# rf_front.net
KiCad netlist of a schematic drawn in EAGLE
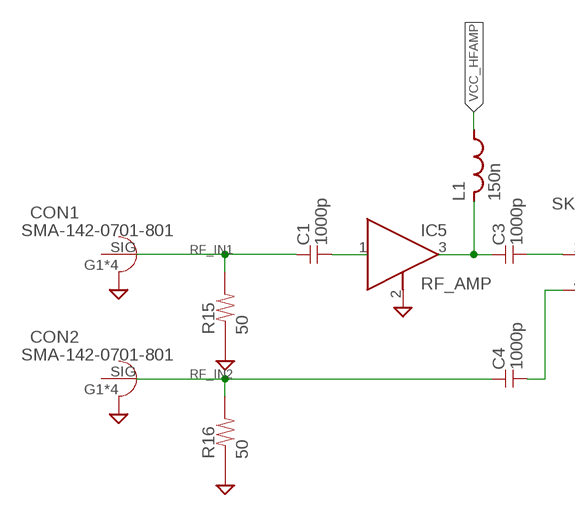
[diagram p0: schematic, sheet 1, part 1 of 2]
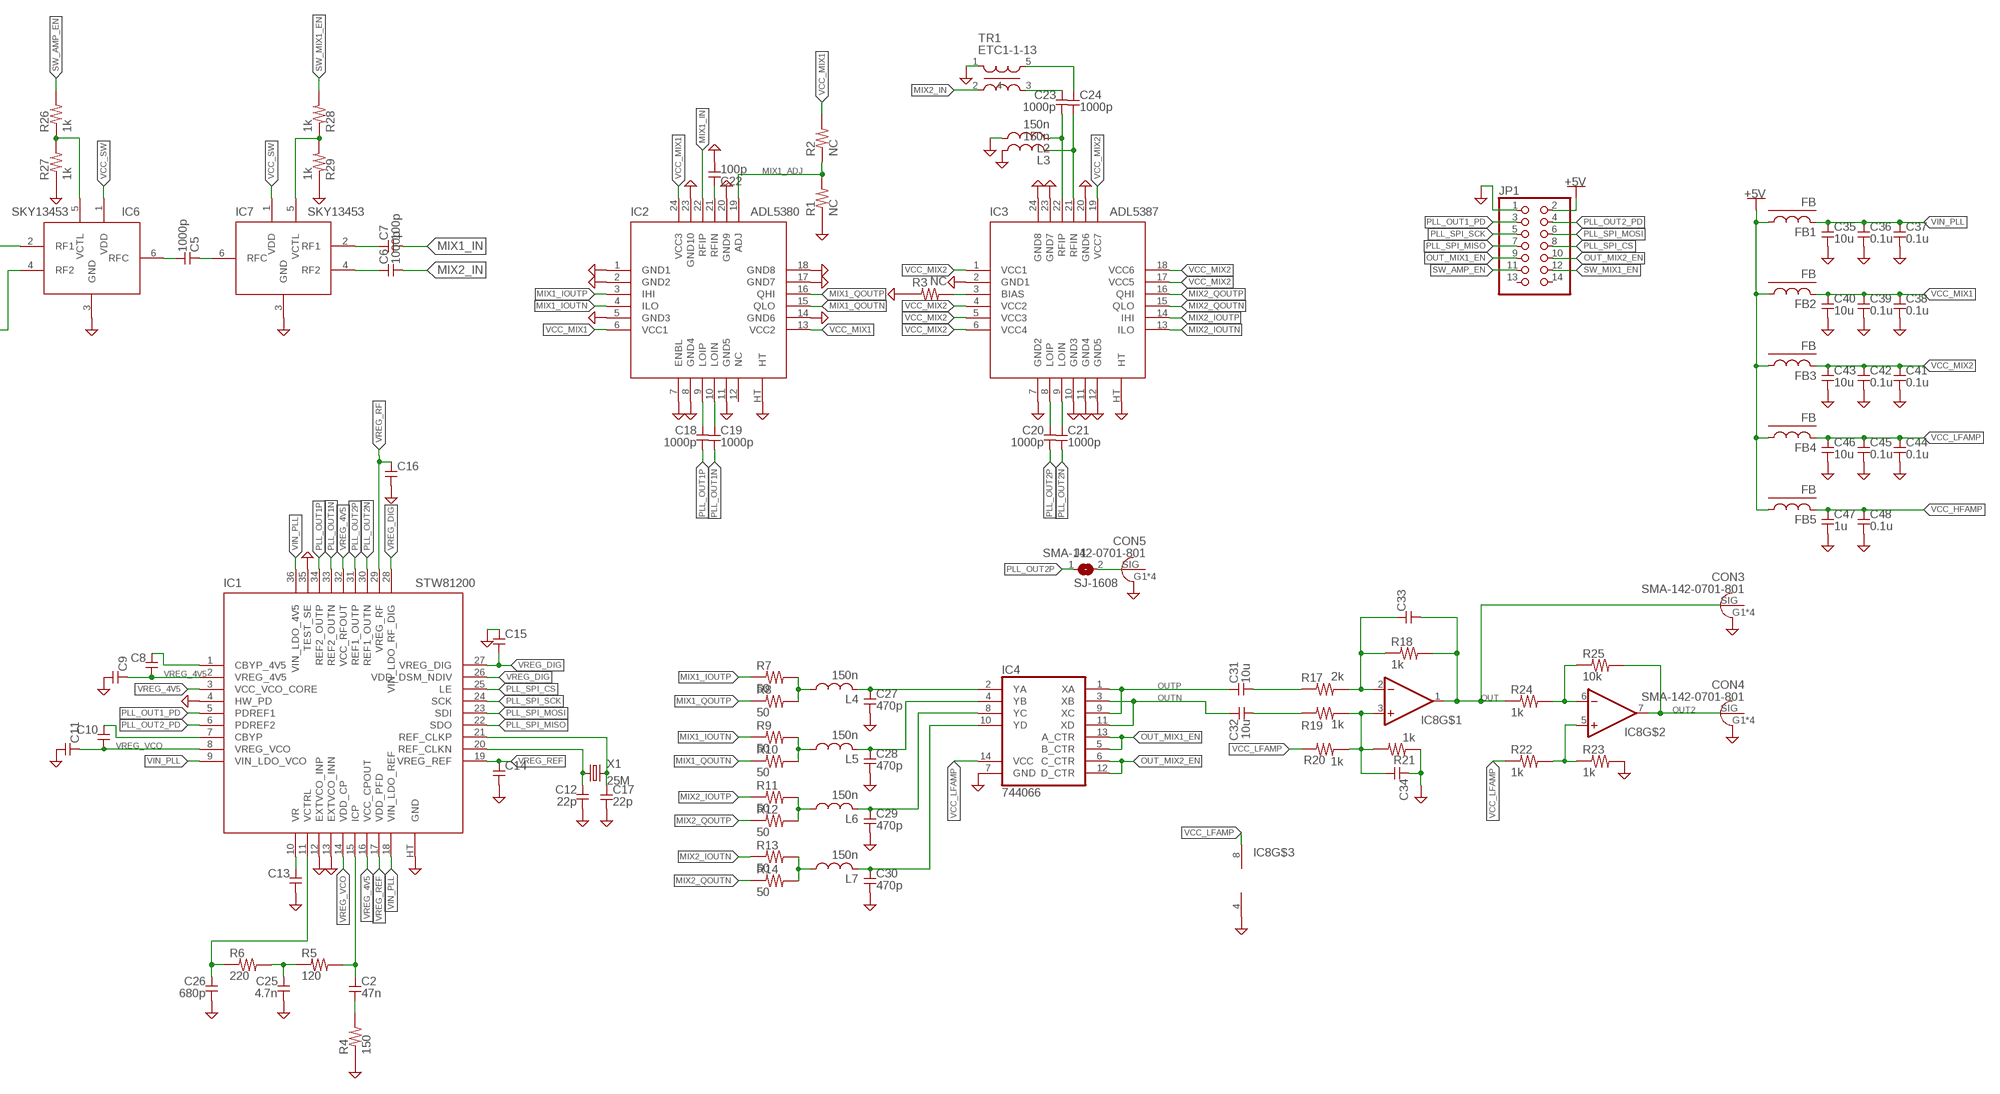
[diagram p1: schematic, sheet 1, part 2 of 2]

(export (version "E")
  (design (tool "Eeschema 10.0.6"))
  (components
    (comp (ref "C1")
      (value "1000p")
      (footprint "eagle-import:1608")
      (libsource (lib "eagle-import") (part "C-1608"))
    )
    (comp (ref "C2")
      (value "47n")
      (footprint "eagle-import:1608")
      (libsource (lib "eagle-import") (part "C-1608"))
    )
    (comp (ref "C3")
      (value "1000p")
      (footprint "eagle-import:1608")
      (libsource (lib "eagle-import") (part "C-1608"))
    )
    (comp (ref "C4")
      (value "1000p")
      (footprint "eagle-import:1608")
      (libsource (lib "eagle-import") (part "C-1608"))
    )
    (comp (ref "C5")
      (value "1000p")
      (footprint "eagle-import:1608")
      (libsource (lib "eagle-import") (part "C-1608"))
    )
    (comp (ref "C6")
      (value "1000p")
      (footprint "eagle-import:1608")
      (libsource (lib "eagle-import") (part "C-1608"))
    )
    (comp (ref "C7")
      (value "100p")
      (footprint "eagle-import:1608")
      (libsource (lib "eagle-import") (part "C-1608"))
    )
    (comp (ref "C8")
      (value "C-1608")
      (footprint "eagle-import:1608")
      (libsource (lib "eagle-import") (part "C-1608"))
    )
    (comp (ref "C9")
      (value "C-1608")
      (footprint "eagle-import:1608")
      (libsource (lib "eagle-import") (part "C-1608"))
    )
    (comp (ref "C10")
      (value "C-1608")
      (footprint "eagle-import:1608")
      (libsource (lib "eagle-import") (part "C-1608"))
    )
    (comp (ref "C11")
      (value "C-1608")
      (footprint "eagle-import:1608")
      (libsource (lib "eagle-import") (part "C-1608"))
    )
    (comp (ref "C12")
      (value "22p")
      (footprint "eagle-import:1608")
      (libsource (lib "eagle-import") (part "C-1608"))
    )
    (comp (ref "C13")
      (value "C-1608")
      (footprint "eagle-import:1608")
      (libsource (lib "eagle-import") (part "C-1608"))
    )
    (comp (ref "C14")
      (value "C-1608")
      (footprint "eagle-import:1608")
      (libsource (lib "eagle-import") (part "C-1608"))
    )
    (comp (ref "C15")
      (value "C-1608")
      (footprint "eagle-import:1608")
      (libsource (lib "eagle-import") (part "C-1608"))
    )
    (comp (ref "C16")
      (value "C-1608")
      (footprint "eagle-import:1608")
      (libsource (lib "eagle-import") (part "C-1608"))
    )
    (comp (ref "C17")
      (value "22p")
      (footprint "eagle-import:1608")
      (libsource (lib "eagle-import") (part "C-1608"))
    )
    (comp (ref "C18")
      (value "1000p")
      (footprint "eagle-import:1608")
      (libsource (lib "eagle-import") (part "C-1608"))
    )
    (comp (ref "C19")
      (value "1000p")
      (footprint "eagle-import:1608")
      (libsource (lib "eagle-import") (part "C-1608"))
    )
    (comp (ref "C20")
      (value "1000p")
      (footprint "eagle-import:1608")
      (libsource (lib "eagle-import") (part "C-1608"))
    )
    (comp (ref "C21")
      (value "1000p")
      (footprint "eagle-import:1608")
      (libsource (lib "eagle-import") (part "C-1608"))
    )
    (comp (ref "C22")
      (value "100p")
      (footprint "eagle-import:1608")
      (libsource (lib "eagle-import") (part "C-1608"))
    )
    (comp (ref "C23")
      (value "1000p")
      (footprint "eagle-import:1608")
      (libsource (lib "eagle-import") (part "C-1608"))
    )
    (comp (ref "C24")
      (value "1000p")
      (footprint "eagle-import:1608")
      (libsource (lib "eagle-import") (part "C-1608"))
    )
    (comp (ref "C25")
      (value "4.7n")
      (footprint "eagle-import:1608")
      (libsource (lib "eagle-import") (part "C-1608"))
    )
    (comp (ref "C26")
      (value "680p")
      (footprint "eagle-import:1608")
      (libsource (lib "eagle-import") (part "C-1608"))
    )
    (comp (ref "C27")
      (value "470p")
      (footprint "eagle-import:1608")
      (libsource (lib "eagle-import") (part "C-1608"))
    )
    (comp (ref "C28")
      (value "470p")
      (footprint "eagle-import:1608")
      (libsource (lib "eagle-import") (part "C-1608"))
    )
    (comp (ref "C29")
      (value "470p")
      (footprint "eagle-import:1608")
      (libsource (lib "eagle-import") (part "C-1608"))
    )
    (comp (ref "C30")
      (value "470p")
      (footprint "eagle-import:1608")
      (libsource (lib "eagle-import") (part "C-1608"))
    )
    (comp (ref "C31")
      (value "10u")
      (footprint "eagle-import:2012")
      (libsource (lib "eagle-import") (part "C-2012"))
    )
    (comp (ref "C32")
      (value "10u")
      (footprint "eagle-import:2012")
      (libsource (lib "eagle-import") (part "C-2012"))
    )
    (comp (ref "C33")
      (value "C-1608")
      (footprint "eagle-import:1608")
      (libsource (lib "eagle-import") (part "C-1608"))
    )
    (comp (ref "C34")
      (value "C-1608")
      (footprint "eagle-import:1608")
      (libsource (lib "eagle-import") (part "C-1608"))
    )
    (comp (ref "C35")
      (value "10u")
      (footprint "eagle-import:2012")
      (libsource (lib "eagle-import") (part "C-2012"))
    )
    (comp (ref "C36")
      (value "0.1u")
      (footprint "eagle-import:1608")
      (libsource (lib "eagle-import") (part "C-1608"))
    )
    (comp (ref "C37")
      (value "0.1u")
      (footprint "eagle-import:1608")
      (libsource (lib "eagle-import") (part "C-1608"))
    )
    (comp (ref "C38")
      (value "0.1u")
      (footprint "eagle-import:1608")
      (libsource (lib "eagle-import") (part "C-1608"))
    )
    (comp (ref "C39")
      (value "0.1u")
      (footprint "eagle-import:1608")
      (libsource (lib "eagle-import") (part "C-1608"))
    )
    (comp (ref "C40")
      (value "10u")
      (footprint "eagle-import:2012")
      (libsource (lib "eagle-import") (part "C-2012"))
    )
    (comp (ref "C41")
      (value "0.1u")
      (footprint "eagle-import:1608")
      (libsource (lib "eagle-import") (part "C-1608"))
    )
    (comp (ref "C42")
      (value "0.1u")
      (footprint "eagle-import:1608")
      (libsource (lib "eagle-import") (part "C-1608"))
    )
    (comp (ref "C43")
      (value "10u")
      (footprint "eagle-import:2012")
      (libsource (lib "eagle-import") (part "C-2012"))
    )
    (comp (ref "C44")
      (value "0.1u")
      (footprint "eagle-import:1608")
      (libsource (lib "eagle-import") (part "C-1608"))
    )
    (comp (ref "C45")
      (value "0.1u")
      (footprint "eagle-import:1608")
      (libsource (lib "eagle-import") (part "C-1608"))
    )
    (comp (ref "C46")
      (value "10u")
      (footprint "eagle-import:2012")
      (libsource (lib "eagle-import") (part "C-2012"))
    )
    (comp (ref "C47")
      (value "1u")
      (footprint "eagle-import:1608")
      (libsource (lib "eagle-import") (part "C-1608"))
    )
    (comp (ref "C48")
      (value "0.1u")
      (footprint "eagle-import:1608")
      (libsource (lib "eagle-import") (part "C-1608"))
    )
    (comp (ref "CON1")
      (value "SMA-142-0701-801")
      (footprint "eagle-import:SMA-142-0701-801")
      (libsource (lib "eagle-import") (part "SMA-142-0701-801"))
    )
    (comp (ref "CON2")
      (value "SMA-142-0701-801")
      (footprint "eagle-import:SMA-142-0701-801")
      (libsource (lib "eagle-import") (part "SMA-142-0701-801"))
    )
    (comp (ref "CON3")
      (value "SMA-142-0701-801")
      (footprint "eagle-import:SMA-142-0701-801")
      (libsource (lib "eagle-import") (part "SMA-142-0701-801"))
    )
    (comp (ref "CON4")
      (value "SMA-142-0701-801")
      (footprint "eagle-import:SMA-142-0701-801")
      (libsource (lib "eagle-import") (part "SMA-142-0701-801"))
    )
    (comp (ref "CON5")
      (value "SMA-142-0701-801")
      (footprint "eagle-import:SMA-142-0701-801")
      (libsource (lib "eagle-import") (part "SMA-142-0701-801"))
    )
    (comp (ref "FB1")
      (value "FB")
      (footprint "eagle-import:1608-J")
      (libsource (lib "eagle-import") (part "FB"))
    )
    (comp (ref "FB2")
      (value "FB")
      (footprint "eagle-import:1608-J")
      (libsource (lib "eagle-import") (part "FB"))
    )
    (comp (ref "FB3")
      (value "FB")
      (footprint "eagle-import:1608-J")
      (libsource (lib "eagle-import") (part "FB"))
    )
    (comp (ref "FB4")
      (value "FB")
      (footprint "eagle-import:1608-J")
      (libsource (lib "eagle-import") (part "FB"))
    )
    (comp (ref "FB5")
      (value "FB")
      (footprint "eagle-import:1608-J")
      (libsource (lib "eagle-import") (part "FB"))
    )
    (comp (ref "IC1")
      (value "STW81200")
      (footprint "eagle-import:VFQFPN36")
      (libsource (lib "eagle-import") (part "STW81200"))
    )
    (comp (ref "IC2")
      (value "ADL5380")
      (footprint "eagle-import:LFCSP24")
      (libsource (lib "eagle-import") (part "ADL5380"))
    )
    (comp (ref "IC3")
      (value "ADL5387")
      (footprint "eagle-import:LFCSP24")
      (libsource (lib "eagle-import") (part "ADL5387"))
    )
    (comp (ref "IC4")
      (value "744066")
      (footprint "eagle-import:SOP14")
      (libsource (lib "eagle-import") (part "744066"))
    )
    (comp (ref "IC5")
      (value "RF_AMP")
      (footprint "eagle-import:SOT89")
      (libsource (lib "eagle-import") (part "RF_AMP"))
    )
    (comp (ref "IC6")
      (value "SKY13453")
      (footprint "eagle-import:SKY13453")
      (libsource (lib "eagle-import") (part "SKY13453"))
    )
    (comp (ref "IC7")
      (value "SKY13453")
      (footprint "eagle-import:SKY13453")
      (libsource (lib "eagle-import") (part "SKY13453"))
    )
    (comp (ref "IC8")
      (value "OPA-2-SOP")
      (footprint "eagle-import:SOP8")
      (libsource (lib "eagle-import") (part "OPA-2-SOP"))
    )
    (comp (ref "J1")
      (value "SJ-1608")
      (footprint "eagle-import:1608-J")
      (libsource (lib "eagle-import") (part "SJ-1608"))
    )
    (comp (ref "JP1")
      (value "PINHD-2X7")
      (footprint "eagle-import:2X07")
      (libsource (lib "eagle-import") (part "PINHD-2X7"))
    )
    (comp (ref "L1")
      (value "150n")
      (footprint "eagle-import:1608")
      (libsource (lib "eagle-import") (part "L-1608"))
    )
    (comp (ref "L2")
      (value "150n")
      (footprint "eagle-import:1608")
      (libsource (lib "eagle-import") (part "L-1608"))
    )
    (comp (ref "L3")
      (value "150n")
      (footprint "eagle-import:1608")
      (libsource (lib "eagle-import") (part "L-1608"))
    )
    (comp (ref "L4")
      (value "150n")
      (footprint "eagle-import:1608")
      (libsource (lib "eagle-import") (part "L-1608"))
    )
    (comp (ref "L5")
      (value "150n")
      (footprint "eagle-import:1608")
      (libsource (lib "eagle-import") (part "L-1608"))
    )
    (comp (ref "L6")
      (value "150n")
      (footprint "eagle-import:1608")
      (libsource (lib "eagle-import") (part "L-1608"))
    )
    (comp (ref "L7")
      (value "150n")
      (footprint "eagle-import:1608")
      (libsource (lib "eagle-import") (part "L-1608"))
    )
    (comp (ref "R1")
      (value "NC")
      (footprint "eagle-import:1608")
      (libsource (lib "eagle-import") (part "R-1608"))
    )
    (comp (ref "R2")
      (value "NC")
      (footprint "eagle-import:1608")
      (libsource (lib "eagle-import") (part "R-1608"))
    )
    (comp (ref "R3")
      (value "NC")
      (footprint "eagle-import:1608")
      (libsource (lib "eagle-import") (part "R-1608"))
    )
    (comp (ref "R4")
      (value "150")
      (footprint "eagle-import:1608")
      (libsource (lib "eagle-import") (part "R-1608"))
    )
    (comp (ref "R5")
      (value "120")
      (footprint "eagle-import:1608")
      (libsource (lib "eagle-import") (part "R-1608"))
    )
    (comp (ref "R6")
      (value "220")
      (footprint "eagle-import:1608")
      (libsource (lib "eagle-import") (part "R-1608"))
    )
    (comp (ref "R7")
      (value "50")
      (footprint "eagle-import:1608")
      (libsource (lib "eagle-import") (part "R-1608"))
    )
    (comp (ref "R8")
      (value "50")
      (footprint "eagle-import:1608")
      (libsource (lib "eagle-import") (part "R-1608"))
    )
    (comp (ref "R9")
      (value "50")
      (footprint "eagle-import:1608")
      (libsource (lib "eagle-import") (part "R-1608"))
    )
    (comp (ref "R10")
      (value "50")
      (footprint "eagle-import:1608")
      (libsource (lib "eagle-import") (part "R-1608"))
    )
    (comp (ref "R11")
      (value "50")
      (footprint "eagle-import:1608")
      (libsource (lib "eagle-import") (part "R-1608"))
    )
    (comp (ref "R12")
      (value "50")
      (footprint "eagle-import:1608")
      (libsource (lib "eagle-import") (part "R-1608"))
    )
    (comp (ref "R13")
      (value "50")
      (footprint "eagle-import:1608")
      (libsource (lib "eagle-import") (part "R-1608"))
    )
    (comp (ref "R14")
      (value "50")
      (footprint "eagle-import:1608")
      (libsource (lib "eagle-import") (part "R-1608"))
    )
    (comp (ref "R15")
      (value "50")
      (footprint "eagle-import:1608")
      (libsource (lib "eagle-import") (part "R-1608"))
    )
    (comp (ref "R16")
      (value "50")
      (footprint "eagle-import:1608")
      (libsource (lib "eagle-import") (part "R-1608"))
    )
    (comp (ref "R17")
      (value "2k")
      (footprint "eagle-import:1608")
      (libsource (lib "eagle-import") (part "R-1608"))
    )
    (comp (ref "R18")
      (value "1k")
      (footprint "eagle-import:1608")
      (libsource (lib "eagle-import") (part "R-1608"))
    )
    (comp (ref "R19")
      (value "1k")
      (footprint "eagle-import:1608")
      (libsource (lib "eagle-import") (part "R-1608"))
    )
    (comp (ref "R20")
      (value "1k")
      (footprint "eagle-import:1608")
      (libsource (lib "eagle-import") (part "R-1608"))
    )
    (comp (ref "R21")
      (value "1k")
      (footprint "eagle-import:1608")
      (libsource (lib "eagle-import") (part "R-1608"))
    )
    (comp (ref "R22")
      (value "1k")
      (footprint "eagle-import:1608")
      (libsource (lib "eagle-import") (part "R-1608"))
    )
    (comp (ref "R23")
      (value "1k")
      (footprint "eagle-import:1608")
      (libsource (lib "eagle-import") (part "R-1608"))
    )
    (comp (ref "R24")
      (value "1k")
      (footprint "eagle-import:1608")
      (libsource (lib "eagle-import") (part "R-1608"))
    )
    (comp (ref "R25")
      (value "10k")
      (footprint "eagle-import:1608")
      (libsource (lib "eagle-import") (part "R-1608"))
    )
    (comp (ref "R26")
      (value "1k")
      (footprint "eagle-import:1608")
      (libsource (lib "eagle-import") (part "R-1608"))
    )
    (comp (ref "R27")
      (value "1k")
      (footprint "eagle-import:1608")
      (libsource (lib "eagle-import") (part "R-1608"))
    )
    (comp (ref "R28")
      (value "1k")
      (footprint "eagle-import:1608")
      (libsource (lib "eagle-import") (part "R-1608"))
    )
    (comp (ref "R29")
      (value "1k")
      (footprint "eagle-import:1608")
      (libsource (lib "eagle-import") (part "R-1608"))
    )
    (comp (ref "TR1")
      (value "ETC1-1-13")
      (footprint "eagle-import:ETC1-1-13")
      (libsource (lib "eagle-import") (part "ETC1-1-13"))
    )
    (comp (ref "X1")
      (value "25M")
      (footprint "eagle-import:HC49_S")
      (libsource (lib "eagle-import") (part "CRYSTALHC49S"))
    )
  )
  (nets
    (net (code "1") (name "+5V") (class "Default")
      (node (ref "FB1") (pin "1") (pinfunction "1_1") (pintype "passive"))
      (node (ref "FB2") (pin "1") (pinfunction "1_1") (pintype "passive"))
      (node (ref "FB3") (pin "1") (pinfunction "1_1") (pintype "passive"))
      (node (ref "FB4") (pin "1") (pinfunction "1_1") (pintype "passive"))
      (node (ref "FB5") (pin "1") (pinfunction "1_1") (pintype "passive"))
      (node (ref "JP1") (pin "2") (pinfunction "2_2") (pintype "passive"))
    )
    (net (code "2") (name "/MIX1_ADJ") (class "Default")
      (node (ref "IC2") (pin "19") (pinfunction "ADJ_19") (pintype "bidirectional"))
      (node (ref "R1") (pin "2") (pinfunction "2_2") (pintype "passive"))
      (node (ref "R2") (pin "1") (pinfunction "1_1") (pintype "passive"))
    )
    (net (code "3") (name "/OUT") (class "Default")
      (node (ref "C33") (pin "2") (pinfunction "2_2") (pintype "passive"))
      (node (ref "CON3") (pin "SIG") (pinfunction "SIG_SIG") (pintype "passive"))
      (node (ref "IC8") (pin "1") (pinfunction "OUT_1") (pintype "output"))
      (node (ref "R18") (pin "2") (pinfunction "2_2") (pintype "passive"))
      (node (ref "R24") (pin "1") (pinfunction "1_1") (pintype "passive"))
    )
    (net (code "4") (name "/OUT2") (class "Default")
      (node (ref "CON4") (pin "SIG") (pinfunction "SIG_SIG") (pintype "passive"))
      (node (ref "IC8") (pin "7") (pinfunction "OUT_7") (pintype "output"))
      (node (ref "R25") (pin "2") (pinfunction "2_2") (pintype "passive"))
    )
    (net (code "5") (name "/OUTN") (class "Default")
      (node (ref "C32") (pin "1") (pinfunction "1_1") (pintype "passive"))
      (node (ref "IC4") (pin "11") (pinfunction "XD_11") (pintype "bidirectional"))
      (node (ref "IC4") (pin "3") (pinfunction "XB_3") (pintype "bidirectional"))
    )
    (net (code "6") (name "/OUTP") (class "Default")
      (node (ref "C31") (pin "1") (pinfunction "1_1") (pintype "passive"))
      (node (ref "IC4") (pin "1") (pinfunction "XA_1") (pintype "bidirectional"))
      (node (ref "IC4") (pin "9") (pinfunction "XC_9") (pintype "bidirectional"))
    )
    (net (code "7") (name "/RF_IN1") (class "Default")
      (node (ref "C1") (pin "1") (pinfunction "1_1") (pintype "passive"))
      (node (ref "CON1") (pin "SIG") (pinfunction "SIG_SIG") (pintype "passive"))
      (node (ref "R15") (pin "2") (pinfunction "2_2") (pintype "passive"))
    )
    (net (code "8") (name "/RF_IN2") (class "Default")
      (node (ref "C4") (pin "1") (pinfunction "1_1") (pintype "passive"))
      (node (ref "CON2") (pin "SIG") (pinfunction "SIG_SIG") (pintype "passive"))
      (node (ref "R16") (pin "2") (pinfunction "2_2") (pintype "passive"))
    )
    (net (code "9") (name "GND") (class "Default")
      (node (ref "C11") (pin "2") (pinfunction "2_2") (pintype "passive"))
      (node (ref "C12") (pin "2") (pinfunction "2_2") (pintype "passive"))
      (node (ref "C13") (pin "2") (pinfunction "2_2") (pintype "passive"))
      (node (ref "C14") (pin "2") (pinfunction "2_2") (pintype "passive"))
      (node (ref "C15") (pin "1") (pinfunction "1_1") (pintype "passive"))
      (node (ref "C16") (pin "2") (pinfunction "2_2") (pintype "passive"))
      (node (ref "C17") (pin "2") (pinfunction "2_2") (pintype "passive"))
      (node (ref "C22") (pin "2") (pinfunction "2_2") (pintype "passive"))
      (node (ref "C25") (pin "2") (pinfunction "2_2") (pintype "passive"))
      (node (ref "C26") (pin "2") (pinfunction "2_2") (pintype "passive"))
      (node (ref "C27") (pin "2") (pinfunction "2_2") (pintype "passive"))
      (node (ref "C28") (pin "2") (pinfunction "2_2") (pintype "passive"))
      (node (ref "C29") (pin "2") (pinfunction "2_2") (pintype "passive"))
      (node (ref "C30") (pin "2") (pinfunction "2_2") (pintype "passive"))
      (node (ref "C34") (pin "1") (pinfunction "1_1") (pintype "passive"))
      (node (ref "C35") (pin "2") (pinfunction "2_2") (pintype "passive"))
      (node (ref "C36") (pin "2") (pinfunction "2_2") (pintype "passive"))
      (node (ref "C37") (pin "2") (pinfunction "2_2") (pintype "passive"))
      (node (ref "C38") (pin "2") (pinfunction "2_2") (pintype "passive"))
      (node (ref "C39") (pin "2") (pinfunction "2_2") (pintype "passive"))
      (node (ref "C40") (pin "2") (pinfunction "2_2") (pintype "passive"))
      (node (ref "C41") (pin "2") (pinfunction "2_2") (pintype "passive"))
      (node (ref "C42") (pin "2") (pinfunction "2_2") (pintype "passive"))
      (node (ref "C43") (pin "2") (pinfunction "2_2") (pintype "passive"))
      (node (ref "C44") (pin "2") (pinfunction "2_2") (pintype "passive"))
      (node (ref "C45") (pin "2") (pinfunction "2_2") (pintype "passive"))
      (node (ref "C46") (pin "2") (pinfunction "2_2") (pintype "passive"))
      (node (ref "C47") (pin "2") (pinfunction "2_2") (pintype "passive"))
      (node (ref "C48") (pin "2") (pinfunction "2_2") (pintype "passive"))
      (node (ref "C9") (pin "2") (pinfunction "2_2") (pintype "passive"))
      (node (ref "CON1") (pin "G1") (pinfunction "GND_G1") (pintype "passive"))
      (node (ref "CON1") (pin "G2") (pinfunction "GND_G2") (pintype "passive"))
      (node (ref "CON1") (pin "G3") (pinfunction "GND_G3") (pintype "passive"))
      (node (ref "CON1") (pin "G4") (pinfunction "GND_G4") (pintype "passive"))
      (node (ref "CON2") (pin "G1") (pinfunction "GND_G1") (pintype "passive"))
      (node (ref "CON2") (pin "G2") (pinfunction "GND_G2") (pintype "passive"))
      (node (ref "CON2") (pin "G3") (pinfunction "GND_G3") (pintype "passive"))
      (node (ref "CON2") (pin "G4") (pinfunction "GND_G4") (pintype "passive"))
      (node (ref "CON3") (pin "G1") (pinfunction "GND_G1") (pintype "passive"))
      (node (ref "CON3") (pin "G2") (pinfunction "GND_G2") (pintype "passive"))
      (node (ref "CON3") (pin "G3") (pinfunction "GND_G3") (pintype "passive"))
      (node (ref "CON3") (pin "G4") (pinfunction "GND_G4") (pintype "passive"))
      (node (ref "CON4") (pin "G1") (pinfunction "GND_G1") (pintype "passive"))
      (node (ref "CON4") (pin "G2") (pinfunction "GND_G2") (pintype "passive"))
      (node (ref "CON4") (pin "G3") (pinfunction "GND_G3") (pintype "passive"))
      (node (ref "CON4") (pin "G4") (pinfunction "GND_G4") (pintype "passive"))
      (node (ref "CON5") (pin "G1") (pinfunction "GND_G1") (pintype "passive"))
      (node (ref "CON5") (pin "G2") (pinfunction "GND_G2") (pintype "passive"))
      (node (ref "CON5") (pin "G3") (pinfunction "GND_G3") (pintype "passive"))
      (node (ref "CON5") (pin "G4") (pinfunction "GND_G4") (pintype "passive"))
      (node (ref "IC1") (pin "12") (pinfunction "EXTVCO_INP_12") (pintype "input"))
      (node (ref "IC1") (pin "13") (pinfunction "EXTVCO_INN_13") (pintype "input"))
      (node (ref "IC1") (pin "35") (pinfunction "TEST_SE_35") (pintype "input"))
      (node (ref "IC1") (pin "4") (pinfunction "HW_PD_4") (pintype "input"))
      (node (ref "IC1") (pin "HT") (pinfunction "GND_HT") (pintype "power_in"))
      (node (ref "IC2") (pin "1") (pinfunction "GND1_1") (pintype "power_in"))
      (node (ref "IC2") (pin "11") (pinfunction "GND5_11") (pintype "power_in"))
      (node (ref "IC2") (pin "14") (pinfunction "GND6_14") (pintype "power_in"))
      (node (ref "IC2") (pin "17") (pinfunction "GND7_17") (pintype "power_in"))
      (node (ref "IC2") (pin "18") (pinfunction "GND8_18") (pintype "power_in"))
      (node (ref "IC2") (pin "2") (pinfunction "GND2_2") (pintype "power_in"))
      (node (ref "IC2") (pin "20") (pinfunction "GND9_20") (pintype "power_in"))
      (node (ref "IC2") (pin "23") (pinfunction "GND10_23") (pintype "power_in"))
      (node (ref "IC2") (pin "5") (pinfunction "GND3_5") (pintype "power_in"))
      (node (ref "IC2") (pin "7") (pinfunction "ENBL_7") (pintype "input"))
      (node (ref "IC2") (pin "8") (pinfunction "GND4_8") (pintype "power_in"))
      (node (ref "IC2") (pin "HT") (pinfunction "HT_HT") (pintype "passive"))
      (node (ref "IC3") (pin "10") (pinfunction "GND3_10") (pintype "power_in"))
      (node (ref "IC3") (pin "11") (pinfunction "GND4_11") (pintype "power_in"))
      (node (ref "IC3") (pin "12") (pinfunction "GND5_12") (pintype "power_in"))
      (node (ref "IC3") (pin "2") (pinfunction "GND1_2") (pintype "power_in"))
      (node (ref "IC3") (pin "20") (pinfunction "GND6_20") (pintype "power_in"))
      (node (ref "IC3") (pin "23") (pinfunction "GND7_23") (pintype "power_in"))
      (node (ref "IC3") (pin "24") (pinfunction "GND8_24") (pintype "power_in"))
      (node (ref "IC3") (pin "7") (pinfunction "GND2_7") (pintype "power_in"))
      (node (ref "IC3") (pin "HT") (pinfunction "HT_HT") (pintype "passive"))
      (node (ref "IC4") (pin "7") (pinfunction "GND_7") (pintype "power_in"))
      (node (ref "IC5") (pin "2") (pinfunction "GND_2") (pintype "power_in"))
      (node (ref "IC6") (pin "3") (pinfunction "GND_3") (pintype "power_in"))
      (node (ref "IC7") (pin "3") (pinfunction "GND_3") (pintype "power_in"))
      (node (ref "IC8") (pin "4") (pinfunction "V-_4") (pintype "power_in"))
      (node (ref "JP1") (pin "1") (pinfunction "1_1") (pintype "passive"))
      (node (ref "L2") (pin "1") (pinfunction "1_1") (pintype "passive"))
      (node (ref "L3") (pin "1") (pinfunction "1_1") (pintype "passive"))
      (node (ref "R1") (pin "1") (pinfunction "1_1") (pintype "passive"))
      (node (ref "R15") (pin "1") (pinfunction "1_1") (pintype "passive"))
      (node (ref "R16") (pin "1") (pinfunction "1_1") (pintype "passive"))
      (node (ref "R21") (pin "1") (pinfunction "1_1") (pintype "passive"))
      (node (ref "R23") (pin "2") (pinfunction "2_2") (pintype "passive"))
      (node (ref "R27") (pin "1") (pinfunction "1_1") (pintype "passive"))
      (node (ref "R29") (pin "1") (pinfunction "1_1") (pintype "passive"))
      (node (ref "R3") (pin "1") (pinfunction "1_1") (pintype "passive"))
      (node (ref "R4") (pin "1") (pinfunction "1_1") (pintype "passive"))
      (node (ref "TR1") (pin "1") (pinfunction "1_1") (pintype "passive"))
    )
    (net (code "10") (name "MIX1_IN") (class "Default")
      (node (ref "C7") (pin "2") (pinfunction "2_2") (pintype "passive"))
      (node (ref "IC2") (pin "22") (pinfunction "RFIP_22") (pintype "input"))
    )
    (net (code "11") (name "MIX1_IOUTN") (class "Default")
      (node (ref "IC2") (pin "4") (pinfunction "ILO_4") (pintype "output"))
      (node (ref "R9") (pin "1") (pinfunction "1_1") (pintype "passive"))
    )
    (net (code "12") (name "MIX1_IOUTP") (class "Default")
      (node (ref "IC2") (pin "3") (pinfunction "IHI_3") (pintype "output"))
      (node (ref "R7") (pin "1") (pinfunction "1_1") (pintype "passive"))
    )
    (net (code "13") (name "MIX1_QOUTN") (class "Default")
      (node (ref "IC2") (pin "15") (pinfunction "QLO_15") (pintype "output"))
      (node (ref "R10") (pin "1") (pinfunction "1_1") (pintype "passive"))
    )
    (net (code "14") (name "MIX1_QOUTP") (class "Default")
      (node (ref "IC2") (pin "16") (pinfunction "QHI_16") (pintype "output"))
      (node (ref "R8") (pin "1") (pinfunction "1_1") (pintype "passive"))
    )
    (net (code "15") (name "MIX2_IN") (class "Default")
      (node (ref "C6") (pin "2") (pinfunction "2_2") (pintype "passive"))
      (node (ref "TR1") (pin "2") (pinfunction "2_2") (pintype "passive"))
    )
    (net (code "16") (name "MIX2_IOUTN") (class "Default")
      (node (ref "IC3") (pin "13") (pinfunction "ILO_13") (pintype "input"))
      (node (ref "R13") (pin "1") (pinfunction "1_1") (pintype "passive"))
    )
    (net (code "17") (name "MIX2_IOUTP") (class "Default")
      (node (ref "IC3") (pin "14") (pinfunction "IHI_14") (pintype "input"))
      (node (ref "R11") (pin "1") (pinfunction "1_1") (pintype "passive"))
    )
    (net (code "18") (name "MIX2_QOUTN") (class "Default")
      (node (ref "IC3") (pin "15") (pinfunction "QLO_15") (pintype "output"))
      (node (ref "R14") (pin "1") (pinfunction "1_1") (pintype "passive"))
    )
    (net (code "19") (name "MIX2_QOUTP") (class "Default")
      (node (ref "IC3") (pin "16") (pinfunction "QHI_16") (pintype "output"))
      (node (ref "R12") (pin "1") (pinfunction "1_1") (pintype "passive"))
    )
    (net (code "20") (name "Net-(C2-Pad2)") (class "Default")
      (node (ref "C2") (pin "2") (pinfunction "2_2") (pintype "passive"))
      (node (ref "R4") (pin "2") (pinfunction "2_2") (pintype "passive"))
    )
    (net (code "21") (name "Net-(C23-Pad1)") (class "Default")
      (node (ref "C23") (pin "1") (pinfunction "1_1") (pintype "passive"))
      (node (ref "TR1") (pin "3") (pinfunction "3_3") (pintype "passive"))
    )
    (net (code "22") (name "Net-(C24-Pad1)") (class "Default")
      (node (ref "C24") (pin "1") (pinfunction "1_1") (pintype "passive"))
      (node (ref "TR1") (pin "5") (pinfunction "5_5") (pintype "passive"))
    )
    (net (code "23") (name "Net-(C25-Pad1)") (class "Default")
      (node (ref "C25") (pin "1") (pinfunction "1_1") (pintype "passive"))
      (node (ref "R5") (pin "1") (pinfunction "1_1") (pintype "passive"))
      (node (ref "R6") (pin "2") (pinfunction "2_2") (pintype "passive"))
    )
    (net (code "24") (name "Net-(C31-Pad2)") (class "Default")
      (node (ref "C31") (pin "2") (pinfunction "2_2") (pintype "passive"))
      (node (ref "R17") (pin "1") (pinfunction "1_1") (pintype "passive"))
    )
    (net (code "25") (name "Net-(C32-Pad2)") (class "Default")
      (node (ref "C32") (pin "2") (pinfunction "2_2") (pintype "passive"))
      (node (ref "R19") (pin "1") (pinfunction "1_1") (pintype "passive"))
    )
    (net (code "26") (name "Net-(CON5-PadSIG)") (class "Default")
      (node (ref "CON5") (pin "SIG") (pinfunction "SIG_SIG") (pintype "passive"))
      (node (ref "J1") (pin "2") (pinfunction "2_2") (pintype "passive"))
    )
    (net (code "27") (name "Net-(IC1-CBYP)") (class "Default")
      (node (ref "C10") (pin "1") (pinfunction "1_1") (pintype "passive"))
      (node (ref "IC1") (pin "7") (pinfunction "CBYP_7") (pintype "passive"))
    )
    (net (code "28") (name "Net-(IC1-CBYP_4V5)") (class "Default")
      (node (ref "C8") (pin "1") (pinfunction "1_1") (pintype "passive"))
      (node (ref "IC1") (pin "1") (pinfunction "CBYP_4V5_1") (pintype "passive"))
    )
    (net (code "29") (name "Net-(IC1-ICP)") (class "Default")
      (node (ref "C2") (pin "1") (pinfunction "1_1") (pintype "passive"))
      (node (ref "IC1") (pin "15") (pinfunction "ICP_15") (pintype "output"))
      (node (ref "R5") (pin "2") (pinfunction "2_2") (pintype "passive"))
    )
    (net (code "30") (name "Net-(IC1-REF_CLKN)") (class "Default")
      (node (ref "C12") (pin "1") (pinfunction "1_1") (pintype "passive"))
      (node (ref "IC1") (pin "20") (pinfunction "REF_CLKN_20") (pintype "input"))
      (node (ref "X1") (pin "1") (pinfunction "1_1") (pintype "passive"))
    )
    (net (code "31") (name "Net-(IC1-REF_CLKP)") (class "Default")
      (node (ref "C17") (pin "1") (pinfunction "1_1") (pintype "passive"))
      (node (ref "IC1") (pin "21") (pinfunction "REF_CLKP_21") (pintype "input"))
      (node (ref "X1") (pin "2") (pinfunction "2_2") (pintype "passive"))
    )
    (net (code "32") (name "Net-(IC1-VCTRL)") (class "Default")
      (node (ref "C26") (pin "1") (pinfunction "1_1") (pintype "passive"))
      (node (ref "IC1") (pin "11") (pinfunction "VCTRL_11") (pintype "passive"))
      (node (ref "R6") (pin "1") (pinfunction "1_1") (pintype "passive"))
    )
    (net (code "33") (name "Net-(IC1-VR)") (class "Default")
      (node (ref "C13") (pin "1") (pinfunction "1_1") (pintype "passive"))
      (node (ref "IC1") (pin "10") (pinfunction "VR_10") (pintype "passive"))
    )
    (net (code "34") (name "Net-(IC2-LOIN)") (class "Default")
      (node (ref "C19") (pin "1") (pinfunction "1_1") (pintype "passive"))
      (node (ref "IC2") (pin "10") (pinfunction "LOIN_10") (pintype "input"))
    )
    (net (code "35") (name "Net-(IC2-LOIP)") (class "Default")
      (node (ref "C18") (pin "1") (pinfunction "1_1") (pintype "passive"))
      (node (ref "IC2") (pin "9") (pinfunction "LOIP_9") (pintype "input"))
    )
    (net (code "36") (name "Net-(IC2-RFIN)") (class "Default")
      (node (ref "C22") (pin "1") (pinfunction "1_1") (pintype "passive"))
      (node (ref "IC2") (pin "21") (pinfunction "RFIN_21") (pintype "input"))
    )
    (net (code "37") (name "Net-(IC3-BIAS)") (class "Default")
      (node (ref "IC3") (pin "3") (pinfunction "BIAS_3") (pintype "passive"))
      (node (ref "R3") (pin "2") (pinfunction "2_2") (pintype "passive"))
    )
    (net (code "38") (name "Net-(IC3-LOIN)") (class "Default")
      (node (ref "C21") (pin "1") (pinfunction "1_1") (pintype "passive"))
      (node (ref "IC3") (pin "9") (pinfunction "LOIN_9") (pintype "input"))
    )
    (net (code "39") (name "Net-(IC3-LOIP)") (class "Default")
      (node (ref "C20") (pin "1") (pinfunction "1_1") (pintype "passive"))
      (node (ref "IC3") (pin "8") (pinfunction "LOIP_8") (pintype "input"))
    )
    (net (code "40") (name "Net-(IC3-RFIN)") (class "Default")
      (node (ref "C24") (pin "2") (pinfunction "2_2") (pintype "passive"))
      (node (ref "IC3") (pin "21") (pinfunction "RFIN_21") (pintype "input"))
      (node (ref "L3") (pin "2") (pinfunction "2_2") (pintype "passive"))
    )
    (net (code "41") (name "Net-(IC3-RFIP)") (class "Default")
      (node (ref "C23") (pin "2") (pinfunction "2_2") (pintype "passive"))
      (node (ref "IC3") (pin "22") (pinfunction "RFIP_22") (pintype "input"))
      (node (ref "L2") (pin "2") (pinfunction "2_2") (pintype "passive"))
    )
    (net (code "42") (name "Net-(IC4-YA)") (class "Default")
      (node (ref "C27") (pin "1") (pinfunction "1_1") (pintype "passive"))
      (node (ref "IC4") (pin "2") (pinfunction "YA_2") (pintype "bidirectional"))
      (node (ref "L4") (pin "2") (pinfunction "2_2") (pintype "passive"))
    )
    (net (code "43") (name "Net-(IC4-YB)") (class "Default")
      (node (ref "C28") (pin "1") (pinfunction "1_1") (pintype "passive"))
      (node (ref "IC4") (pin "4") (pinfunction "YB_4") (pintype "bidirectional"))
      (node (ref "L5") (pin "2") (pinfunction "2_2") (pintype "passive"))
    )
    (net (code "44") (name "Net-(IC4-YC)") (class "Default")
      (node (ref "C29") (pin "1") (pinfunction "1_1") (pintype "passive"))
      (node (ref "IC4") (pin "8") (pinfunction "YC_8") (pintype "bidirectional"))
      (node (ref "L6") (pin "2") (pinfunction "2_2") (pintype "passive"))
    )
    (net (code "45") (name "Net-(IC4-YD)") (class "Default")
      (node (ref "C30") (pin "1") (pinfunction "1_1") (pintype "passive"))
      (node (ref "IC4") (pin "10") (pinfunction "YD_10") (pintype "bidirectional"))
      (node (ref "L7") (pin "2") (pinfunction "2_2") (pintype "passive"))
    )
    (net (code "46") (name "Net-(IC5-IN)") (class "Default")
      (node (ref "C1") (pin "2") (pinfunction "2_2") (pintype "passive"))
      (node (ref "IC5") (pin "1") (pinfunction "IN_1") (pintype "input"))
    )
    (net (code "47") (name "Net-(IC5-OUT)") (class "Default")
      (node (ref "C3") (pin "1") (pinfunction "1_1") (pintype "passive"))
      (node (ref "IC5") (pin "3") (pinfunction "OUT_3") (pintype "output"))
      (node (ref "L1") (pin "2") (pinfunction "2_2") (pintype "passive"))
    )
    (net (code "48") (name "Net-(IC6-RF1)") (class "Default")
      (node (ref "C3") (pin "2") (pinfunction "2_2") (pintype "passive"))
      (node (ref "IC6") (pin "2") (pinfunction "RF1_2") (pintype "passive"))
    )
    (net (code "49") (name "Net-(IC6-RF2)") (class "Default")
      (node (ref "C4") (pin "2") (pinfunction "2_2") (pintype "passive"))
      (node (ref "IC6") (pin "4") (pinfunction "RF2_4") (pintype "passive"))
    )
    (net (code "50") (name "Net-(IC6-RFC)") (class "Default")
      (node (ref "C5") (pin "2") (pinfunction "2_2") (pintype "passive"))
      (node (ref "IC6") (pin "6") (pinfunction "RFC_6") (pintype "passive"))
    )
    (net (code "51") (name "Net-(IC6-VCTL)") (class "Default")
      (node (ref "IC6") (pin "5") (pinfunction "VCTL_5") (pintype "input"))
      (node (ref "R26") (pin "1") (pinfunction "1_1") (pintype "passive"))
      (node (ref "R27") (pin "2") (pinfunction "2_2") (pintype "passive"))
    )
    (net (code "52") (name "Net-(IC7-RF1)") (class "Default")
      (node (ref "C7") (pin "1") (pinfunction "1_1") (pintype "passive"))
      (node (ref "IC7") (pin "2") (pinfunction "RF1_2") (pintype "passive"))
    )
    (net (code "53") (name "Net-(IC7-RF2)") (class "Default")
      (node (ref "C6") (pin "1") (pinfunction "1_1") (pintype "passive"))
      (node (ref "IC7") (pin "4") (pinfunction "RF2_4") (pintype "passive"))
    )
    (net (code "54") (name "Net-(IC7-RFC)") (class "Default")
      (node (ref "C5") (pin "1") (pinfunction "1_1") (pintype "passive"))
      (node (ref "IC7") (pin "6") (pinfunction "RFC_6") (pintype "passive"))
    )
    (net (code "55") (name "Net-(IC7-VCTL)") (class "Default")
      (node (ref "IC7") (pin "5") (pinfunction "VCTL_5") (pintype "input"))
      (node (ref "R28") (pin "1") (pinfunction "1_1") (pintype "passive"))
      (node (ref "R29") (pin "2") (pinfunction "2_2") (pintype "passive"))
    )
    (net (code "56") (name "Net-(IC8A-+IN)") (class "Default")
      (node (ref "C34") (pin "2") (pinfunction "2_2") (pintype "passive"))
      (node (ref "IC8") (pin "3") (pinfunction "+IN_3") (pintype "input"))
      (node (ref "R19") (pin "2") (pinfunction "2_2") (pintype "passive"))
      (node (ref "R20") (pin "1") (pinfunction "1_1") (pintype "passive"))
      (node (ref "R21") (pin "2") (pinfunction "2_2") (pintype "passive"))
    )
    (net (code "57") (name "Net-(IC8A--IN)") (class "Default")
      (node (ref "C33") (pin "1") (pinfunction "1_1") (pintype "passive"))
      (node (ref "IC8") (pin "2") (pinfunction "-IN_2") (pintype "input"))
      (node (ref "R17") (pin "2") (pinfunction "2_2") (pintype "passive"))
      (node (ref "R18") (pin "1") (pinfunction "1_1") (pintype "passive"))
    )
    (net (code "58") (name "Net-(IC8B-+IN)") (class "Default")
      (node (ref "IC8") (pin "5") (pinfunction "+IN_5") (pintype "input"))
      (node (ref "R22") (pin "2") (pinfunction "2_2") (pintype "passive"))
      (node (ref "R23") (pin "1") (pinfunction "1_1") (pintype "passive"))
    )
    (net (code "59") (name "Net-(IC8B--IN)") (class "Default")
      (node (ref "IC8") (pin "6") (pinfunction "-IN_6") (pintype "input"))
      (node (ref "R24") (pin "2") (pinfunction "2_2") (pintype "passive"))
      (node (ref "R25") (pin "1") (pinfunction "1_1") (pintype "passive"))
    )
    (net (code "60") (name "Net-(L4-Pad1)") (class "Default")
      (node (ref "L4") (pin "1") (pinfunction "1_1") (pintype "passive"))
      (node (ref "R7") (pin "2") (pinfunction "2_2") (pintype "passive"))
      (node (ref "R8") (pin "2") (pinfunction "2_2") (pintype "passive"))
    )
    (net (code "61") (name "Net-(L5-Pad1)") (class "Default")
      (node (ref "L5") (pin "1") (pinfunction "1_1") (pintype "passive"))
      (node (ref "R10") (pin "2") (pinfunction "2_2") (pintype "passive"))
      (node (ref "R9") (pin "2") (pinfunction "2_2") (pintype "passive"))
    )
    (net (code "62") (name "Net-(L6-Pad1)") (class "Default")
      (node (ref "L6") (pin "1") (pinfunction "1_1") (pintype "passive"))
      (node (ref "R11") (pin "2") (pinfunction "2_2") (pintype "passive"))
      (node (ref "R12") (pin "2") (pinfunction "2_2") (pintype "passive"))
    )
    (net (code "63") (name "Net-(L7-Pad1)") (class "Default")
      (node (ref "L7") (pin "1") (pinfunction "1_1") (pintype "passive"))
      (node (ref "R13") (pin "2") (pinfunction "2_2") (pintype "passive"))
      (node (ref "R14") (pin "2") (pinfunction "2_2") (pintype "passive"))
    )
    (net (code "64") (name "OUT_MIX1_EN") (class "Default")
      (node (ref "IC4") (pin "13") (pinfunction "A_CTR_13") (pintype "input"))
      (node (ref "IC4") (pin "5") (pinfunction "B_CTR_5") (pintype "input"))
      (node (ref "JP1") (pin "9") (pinfunction "9_9") (pintype "passive"))
    )
    (net (code "65") (name "OUT_MIX2_EN") (class "Default")
      (node (ref "IC4") (pin "12") (pinfunction "D_CTR_12") (pintype "bidirectional"))
      (node (ref "IC4") (pin "6") (pinfunction "C_CTR_6") (pintype "bidirectional"))
      (node (ref "JP1") (pin "10") (pinfunction "10_10") (pintype "passive"))
    )
    (net (code "66") (name "PLL_OUT1N") (class "Default")
      (node (ref "C19") (pin "2") (pinfunction "2_2") (pintype "passive"))
      (node (ref "IC1") (pin "33") (pinfunction "REF2_OUTN_33") (pintype "passive"))
    )
    (net (code "67") (name "PLL_OUT1P") (class "Default")
      (node (ref "C18") (pin "2") (pinfunction "2_2") (pintype "passive"))
      (node (ref "IC1") (pin "34") (pinfunction "REF2_OUTP_34") (pintype "passive"))
    )
    (net (code "68") (name "PLL_OUT1_PD") (class "Default")
      (node (ref "IC1") (pin "5") (pinfunction "PDREF1_5") (pintype "input"))
      (node (ref "JP1") (pin "3") (pinfunction "3_3") (pintype "passive"))
    )
    (net (code "69") (name "PLL_OUT2N") (class "Default")
      (node (ref "C21") (pin "2") (pinfunction "2_2") (pintype "passive"))
      (node (ref "IC1") (pin "30") (pinfunction "REF1_OUTN_30") (pintype "output"))
    )
    (net (code "70") (name "PLL_OUT2P") (class "Default")
      (node (ref "C20") (pin "2") (pinfunction "2_2") (pintype "passive"))
      (node (ref "IC1") (pin "31") (pinfunction "REF1_OUTP_31") (pintype "output"))
      (node (ref "J1") (pin "1") (pinfunction "1_1") (pintype "passive"))
    )
    (net (code "71") (name "PLL_OUT2_PD") (class "Default")
      (node (ref "IC1") (pin "6") (pinfunction "PDREF2_6") (pintype "input"))
      (node (ref "JP1") (pin "4") (pinfunction "4_4") (pintype "passive"))
    )
    (net (code "72") (name "PLL_SPI_CS") (class "Default")
      (node (ref "IC1") (pin "25") (pinfunction "LE_25") (pintype "bidirectional"))
      (node (ref "JP1") (pin "8") (pinfunction "8_8") (pintype "passive"))
    )
    (net (code "73") (name "PLL_SPI_MISO") (class "Default")
      (node (ref "IC1") (pin "22") (pinfunction "SDO_22") (pintype "bidirectional"))
      (node (ref "JP1") (pin "7") (pinfunction "7_7") (pintype "passive"))
    )
    (net (code "74") (name "PLL_SPI_MOSI") (class "Default")
      (node (ref "IC1") (pin "23") (pinfunction "SDI_23") (pintype "bidirectional"))
      (node (ref "JP1") (pin "6") (pinfunction "6_6") (pintype "passive"))
    )
    (net (code "75") (name "PLL_SPI_SCK") (class "Default")
      (node (ref "IC1") (pin "24") (pinfunction "SCK_24") (pintype "bidirectional"))
      (node (ref "JP1") (pin "5") (pinfunction "5_5") (pintype "passive"))
    )
    (net (code "76") (name "SW_AMP_EN") (class "Default")
      (node (ref "JP1") (pin "11") (pinfunction "11_11") (pintype "passive"))
      (node (ref "R26") (pin "2") (pinfunction "2_2") (pintype "passive"))
    )
    (net (code "77") (name "SW_MIX1_EN") (class "Default")
      (node (ref "JP1") (pin "12") (pinfunction "12_12") (pintype "passive"))
      (node (ref "R28") (pin "2") (pinfunction "2_2") (pintype "passive"))
    )
    (net (code "78") (name "VCC_HFAMP") (class "Default")
      (node (ref "C47") (pin "1") (pinfunction "1_1") (pintype "passive"))
      (node (ref "C48") (pin "1") (pinfunction "1_1") (pintype "passive"))
      (node (ref "FB5") (pin "2") (pinfunction "2_2") (pintype "passive"))
      (node (ref "L1") (pin "1") (pinfunction "1_1") (pintype "passive"))
    )
    (net (code "79") (name "VCC_LFAMP") (class "Default")
      (node (ref "C44") (pin "1") (pinfunction "1_1") (pintype "passive"))
      (node (ref "C45") (pin "1") (pinfunction "1_1") (pintype "passive"))
      (node (ref "C46") (pin "1") (pinfunction "1_1") (pintype "passive"))
      (node (ref "FB4") (pin "2") (pinfunction "2_2") (pintype "passive"))
      (node (ref "IC4") (pin "14") (pinfunction "VCC_14") (pintype "power_in"))
      (node (ref "IC8") (pin "8") (pinfunction "V+_8") (pintype "power_in"))
      (node (ref "R20") (pin "2") (pinfunction "2_2") (pintype "passive"))
      (node (ref "R22") (pin "1") (pinfunction "1_1") (pintype "passive"))
    )
    (net (code "80") (name "VCC_MIX1") (class "Default")
      (node (ref "C38") (pin "1") (pinfunction "1_1") (pintype "passive"))
      (node (ref "C39") (pin "1") (pinfunction "1_1") (pintype "passive"))
      (node (ref "C40") (pin "1") (pinfunction "1_1") (pintype "passive"))
      (node (ref "FB2") (pin "2") (pinfunction "2_2") (pintype "passive"))
      (node (ref "IC2") (pin "13") (pinfunction "VCC2_13") (pintype "power_in"))
      (node (ref "IC2") (pin "24") (pinfunction "VCC3_24") (pintype "power_in"))
      (node (ref "IC2") (pin "6") (pinfunction "VCC1_6") (pintype "power_in"))
      (node (ref "R2") (pin "2") (pinfunction "2_2") (pintype "passive"))
    )
    (net (code "81") (name "VCC_MIX2") (class "Default")
      (node (ref "C41") (pin "1") (pinfunction "1_1") (pintype "passive"))
      (node (ref "C42") (pin "1") (pinfunction "1_1") (pintype "passive"))
      (node (ref "C43") (pin "1") (pinfunction "1_1") (pintype "passive"))
      (node (ref "FB3") (pin "2") (pinfunction "2_2") (pintype "passive"))
      (node (ref "IC3") (pin "1") (pinfunction "VCC1_1") (pintype "power_in"))
      (node (ref "IC3") (pin "17") (pinfunction "VCC5_17") (pintype "power_in"))
      (node (ref "IC3") (pin "18") (pinfunction "VCC6_18") (pintype "power_in"))
      (node (ref "IC3") (pin "19") (pinfunction "VCC7_19") (pintype "power_in"))
      (node (ref "IC3") (pin "4") (pinfunction "VCC2_4") (pintype "power_in"))
      (node (ref "IC3") (pin "5") (pinfunction "VCC3_5") (pintype "power_in"))
      (node (ref "IC3") (pin "6") (pinfunction "VCC4_6") (pintype "power_in"))
    )
    (net (code "82") (name "VCC_SW") (class "Default")
      (node (ref "IC6") (pin "1") (pinfunction "VDD_1") (pintype "power_in"))
      (node (ref "IC7") (pin "1") (pinfunction "VDD_1") (pintype "power_in"))
    )
    (net (code "83") (name "VIN_PLL") (class "Default")
      (node (ref "C35") (pin "1") (pinfunction "1_1") (pintype "passive"))
      (node (ref "C36") (pin "1") (pinfunction "1_1") (pintype "passive"))
      (node (ref "C37") (pin "1") (pinfunction "1_1") (pintype "passive"))
      (node (ref "FB1") (pin "2") (pinfunction "2_2") (pintype "passive"))
      (node (ref "IC1") (pin "18") (pinfunction "VIN_LDO_REF_18") (pintype "power_in"))
      (node (ref "IC1") (pin "36") (pinfunction "VIN_LDO_4V5_36") (pintype "power_in"))
      (node (ref "IC1") (pin "9") (pinfunction "VIN_LDO_VCO_9") (pintype "power_in"))
    )
    (net (code "84") (name "VREG_4V5") (class "Default")
      (node (ref "C8") (pin "2") (pinfunction "2_2") (pintype "passive"))
      (node (ref "C9") (pin "1") (pinfunction "1_1") (pintype "passive"))
      (node (ref "IC1") (pin "16") (pinfunction "VCC_CPOUT_16") (pintype "power_in"))
      (node (ref "IC1") (pin "2") (pinfunction "VREG_4V5_2") (pintype "passive"))
      (node (ref "IC1") (pin "3") (pinfunction "VCC_VCO_CORE_3") (pintype "power_in"))
      (node (ref "IC1") (pin "32") (pinfunction "VCC_RFOUT_32") (pintype "power_in"))
    )
    (net (code "85") (name "VREG_DIG") (class "Default")
      (node (ref "C15") (pin "2") (pinfunction "2_2") (pintype "passive"))
      (node (ref "IC1") (pin "26") (pinfunction "VDD_DSM_NDIV_26") (pintype "power_in"))
      (node (ref "IC1") (pin "27") (pinfunction "VREG_DIG_27") (pintype "passive"))
      (node (ref "IC1") (pin "28") (pinfunction "VIN_LDO_RF_DIG_28") (pintype "power_in"))
    )
    (net (code "86") (name "VREG_REF") (class "Default")
      (node (ref "C14") (pin "1") (pinfunction "1_1") (pintype "passive"))
      (node (ref "IC1") (pin "17") (pinfunction "VDD_PFD_17") (pintype "power_in"))
      (node (ref "IC1") (pin "19") (pinfunction "VREG_REF_19") (pintype "passive"))
    )
    (net (code "87") (name "VREG_RF") (class "Default")
      (node (ref "C16") (pin "1") (pinfunction "1_1") (pintype "passive"))
      (node (ref "IC1") (pin "29") (pinfunction "VREG_RF_29") (pintype "passive"))
    )
    (net (code "88") (name "VREG_VCO") (class "Default")
      (node (ref "C10") (pin "2") (pinfunction "2_2") (pintype "passive"))
      (node (ref "C11") (pin "1") (pinfunction "1_1") (pintype "passive"))
      (node (ref "IC1") (pin "14") (pinfunction "VDD_CP_14") (pintype "power_in"))
      (node (ref "IC1") (pin "8") (pinfunction "VREG_VCO_8") (pintype "passive"))
    )
    (net (code "89") (name "unconnected-(IC2-NC-Pad12)") (class "Default")
      (node (ref "IC2") (pin "12") (pinfunction "NC_12") (pintype "passive"))
    )
    (net (code "90") (name "unconnected-(JP1-Pad13)") (class "Default")
      (node (ref "JP1") (pin "13") (pinfunction "13_13") (pintype "passive"))
    )
    (net (code "91") (name "unconnected-(JP1-Pad14)") (class "Default")
      (node (ref "JP1") (pin "14") (pinfunction "14_14") (pintype "passive"))
    )
    (net (code "92") (name "unconnected-(TR1-Pad4)") (class "Default")
      (node (ref "TR1") (pin "4") (pinfunction "4_4") (pintype "passive"))
    )
  )
)
